# teensy_protocol_xl8r_3_2.net
KiCad netlist of a schematic drawn in EAGLE
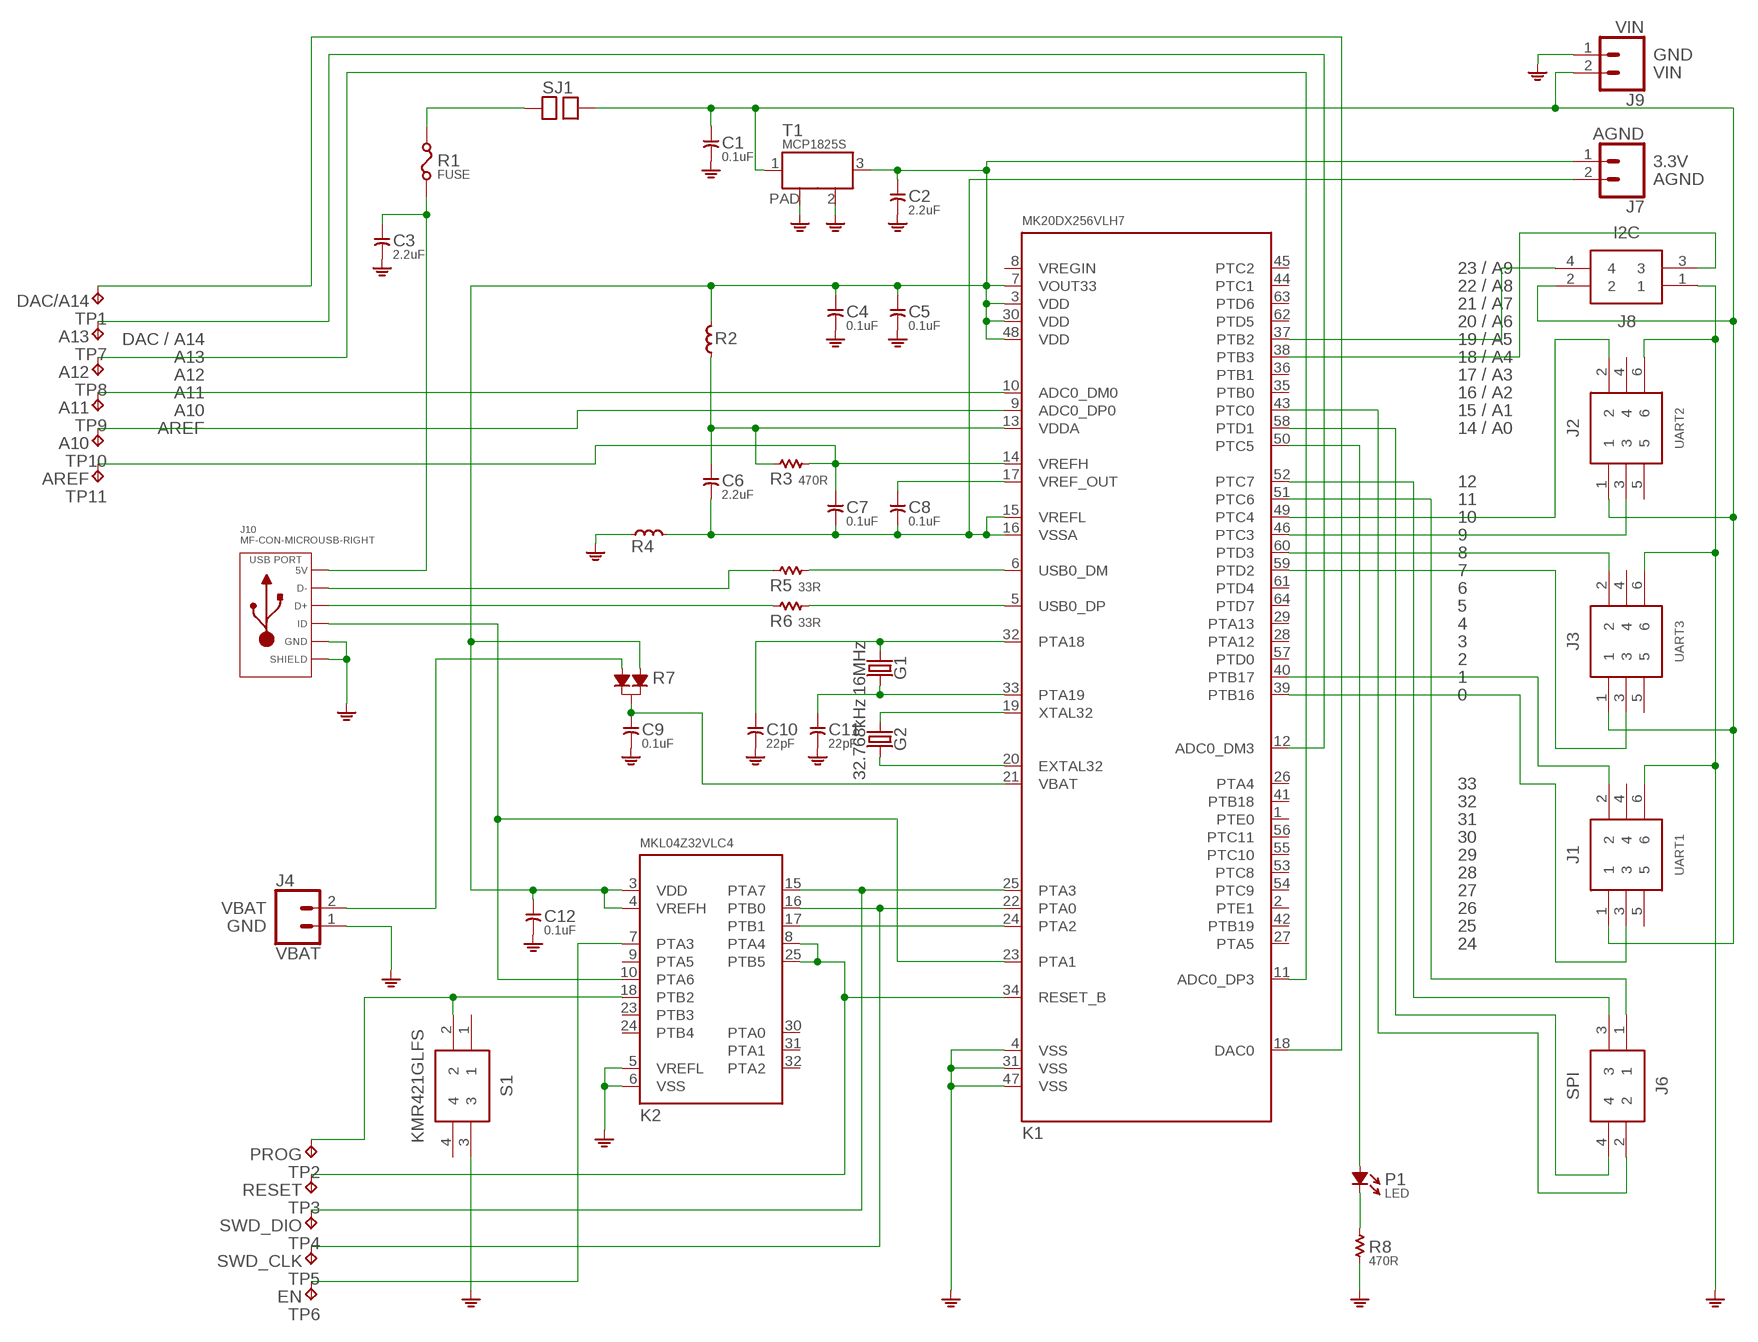
[diagram p0: schematic, sheet 1]

(export (version "E")
  (design (tool "Eeschema 10.0.6"))
  (components
    (comp (ref "C1")
      (value "0.1uF")
      (footprint "eagle-import:C0603")
      (fields (field (name "MF") "Murata Electronics") (field (name "MPN") "GRM188R71C104KA01D"))
      (libsource (lib "eagle-import") (part "CAPACITOR-0.1UF"))
    )
    (comp (ref "C2")
      (value "2.2uF")
      (footprint "eagle-import:C0805")
      (fields (field (name "MF") "Taiyo Yuden") (field (name "MPN") "TMK212B7225KG-TR"))
      (libsource (lib "eagle-import") (part "CAPACITOR-2.2UF"))
    )
    (comp (ref "C3")
      (value "2.2uF")
      (footprint "eagle-import:C0805")
      (fields (field (name "MF") "Taiyo Yuden") (field (name "MPN") "TMK212B7225KG-TR"))
      (libsource (lib "eagle-import") (part "CAPACITOR-2.2UF"))
    )
    (comp (ref "C4")
      (value "0.1uF")
      (footprint "eagle-import:C0603")
      (fields (field (name "MF") "Murata Electronics") (field (name "MPN") "GRM188R71C104KA01D"))
      (libsource (lib "eagle-import") (part "CAPACITOR-0.1UF"))
    )
    (comp (ref "C5")
      (value "0.1uF")
      (footprint "eagle-import:C0603")
      (fields (field (name "MF") "Murata Electronics") (field (name "MPN") "GRM188R71C104KA01D"))
      (libsource (lib "eagle-import") (part "CAPACITOR-0.1UF"))
    )
    (comp (ref "C6")
      (value "2.2uF")
      (footprint "eagle-import:C0805")
      (fields (field (name "MF") "Taiyo Yuden") (field (name "MPN") "TMK212B7225KG-TR"))
      (libsource (lib "eagle-import") (part "CAPACITOR-2.2UF"))
    )
    (comp (ref "C7")
      (value "0.1uF")
      (footprint "eagle-import:C0603")
      (fields (field (name "MF") "Murata Electronics") (field (name "MPN") "GRM188R71C104KA01D"))
      (libsource (lib "eagle-import") (part "CAPACITOR-0.1UF"))
    )
    (comp (ref "C8")
      (value "0.1uF")
      (footprint "eagle-import:C0603")
      (fields (field (name "MF") "Murata Electronics") (field (name "MPN") "GRM188R71C104KA01D"))
      (libsource (lib "eagle-import") (part "CAPACITOR-0.1UF"))
    )
    (comp (ref "C9")
      (value "0.1uF")
      (footprint "eagle-import:C0603")
      (fields (field (name "MF") "Murata Electronics") (field (name "MPN") "GRM188R71C104KA01D"))
      (libsource (lib "eagle-import") (part "CAPACITOR-0.1UF"))
    )
    (comp (ref "C10")
      (value "22pF")
      (footprint "eagle-import:C0603")
      (fields (field (name "MF") "Vishay / Vitramon") (field (name "MPN") "VJ0603A220JXACW1BC"))
      (libsource (lib "eagle-import") (part "CAPACITOR-22PF"))
    )
    (comp (ref "C11")
      (value "22pF")
      (footprint "eagle-import:C0603")
      (fields (field (name "MF") "Vishay / Vitramon") (field (name "MPN") "VJ0603A220JXACW1BC"))
      (libsource (lib "eagle-import") (part "CAPACITOR-22PF"))
    )
    (comp (ref "C12")
      (value "0.1uF")
      (footprint "eagle-import:C0603")
      (fields (field (name "MF") "Murata Electronics") (field (name "MPN") "GRM188R71C104KA01D"))
      (libsource (lib "eagle-import") (part "CAPACITOR-0.1UF"))
    )
    (comp (ref "G1")
      (value "16MHz")
      (footprint "eagle-import:CRYSTAL-SMD-5X3.2-4PAD")
      (libsource (lib "eagle-import") (part "CRYSTAL-16MHZSMD-5X3.2"))
    )
    (comp (ref "G2")
      (value "32.768kHz")
      (footprint "eagle-import:CRYSTAL-SMD-3.2X1.5MM")
      (libsource (lib "eagle-import") (part "CRYSTAL-32.768KHZSMD-3.2X1.5"))
    )
    (comp (ref "J1")
      (value "UART1")
      (footprint "eagle-import:BM06B-GHS-TBT")
      (fields
        (field (name "MANUFACTURER_PART_NUMBER") "BM06B-GHS-TBT(LF)(SN)")
        (field (name "RS_PART_NUMBER") "7521771")
      )
      (libsource (lib "eagle-import") (part "BM06B-GHS-TBT(LF)(SN)"))
    )
    (comp (ref "J2")
      (value "UART2")
      (footprint "eagle-import:BM06B-GHS-TBT")
      (fields
        (field (name "MANUFACTURER_PART_NUMBER") "BM06B-GHS-TBT(LF)(SN)")
        (field (name "RS_PART_NUMBER") "7521771")
      )
      (libsource (lib "eagle-import") (part "BM06B-GHS-TBT(LF)(SN)"))
    )
    (comp (ref "J3")
      (value "UART3")
      (footprint "eagle-import:BM06B-GHS-TBT")
      (fields
        (field (name "MANUFACTURER_PART_NUMBER") "BM06B-GHS-TBT(LF)(SN)")
        (field (name "RS_PART_NUMBER") "7521771")
      )
      (libsource (lib "eagle-import") (part "BM06B-GHS-TBT(LF)(SN)"))
    )
    (comp (ref "J4")
      (value "VBAT")
      (footprint "eagle-import:1X02")
      (libsource (lib "eagle-import") (part "CONN_02"))
    )
    (comp (ref "J6")
      (value "SPI")
      (footprint "eagle-import:BM04B-GHS-TBT")
      (fields
        (field (name "MANUFACTURER_PART_NUMBER") "BM04B-GHS-TBT(LF)(SN)")
        (field (name "RS_PART_NUMBER") "7521769P")
      )
      (libsource (lib "eagle-import") (part "BM04B-GHS-TBT(LF)(SN)"))
    )
    (comp (ref "J7")
      (value "AGND")
      (footprint "eagle-import:1X02")
      (libsource (lib "eagle-import") (part "CONN_02"))
    )
    (comp (ref "J8")
      (value "I2C")
      (footprint "eagle-import:BM04B-GHS-TBT")
      (fields
        (field (name "MANUFACTURER_PART_NUMBER") "BM04B-GHS-TBT(LF)(SN)")
        (field (name "RS_PART_NUMBER") "7521769P")
      )
      (libsource (lib "eagle-import") (part "BM04B-GHS-TBT(LF)(SN)"))
    )
    (comp (ref "J9")
      (value "VIN")
      (footprint "eagle-import:1X02")
      (libsource (lib "eagle-import") (part "CONN_02"))
    )
    (comp (ref "J10")
      (value "MF-CON-MICROUSB-RIGHT")
      (footprint "eagle-import:MICROUSB-RIGHT")
      (fields (field (name "HOUSEPART") "YES"))
      (libsource (lib "eagle-import") (part "USB_MICRO_RIGHT"))
    )
    (comp (ref "K1")
      (value "MK20DX256VLH7")
      (footprint "eagle-import:LQFP64-05")
      (fields (field (name "MF") "NXP"))
      (libsource (lib "eagle-import") (part "MK20DX256VLH7"))
    )
    (comp (ref "K2")
      (value "MKL04Z32VLC4")
      (footprint "eagle-import:LQFP32-08")
      (fields (field (name "MF") "PJRC") (field (name "MPN") "IC_MKL04Z32_TQFP32"))
      (libsource (lib "eagle-import") (part "MKL04Z32VLC4"))
    )
    (comp (ref "P1")
      (value "LED")
      (footprint "eagle-import:LED-0805")
      (fields (field (name "MF") "ROHM Semiconductor") (field (name "MPN") "SML-211DTT86"))
      (libsource (lib "eagle-import") (part "LED"))
    )
    (comp (ref "R1")
      (value "FUSE")
      (footprint "eagle-import:F0805")
      (fields (field (name "MF") "Bel Fuse") (field (name "MPN") "0ZCK0050FF2E"))
      (libsource (lib "eagle-import") (part "FUSE"))
    )
    (comp (ref "R2")
      (value "FERRITE")
      (footprint "eagle-import:L0603")
      (fields (field (name "MF") "Murata Electronics") (field (name "MPN") " BLM18AG601SN1D"))
      (libsource (lib "eagle-import") (part "FERRITE"))
    )
    (comp (ref "R3")
      (value "470R")
      (footprint "eagle-import:R0603")
      (fields (field (name "MF") "Vishay") (field (name "MPN") "CRCW0603470RFKEA"))
      (libsource (lib "eagle-import") (part "RESISTOR-470R"))
    )
    (comp (ref "R4")
      (value "FERRITE")
      (footprint "eagle-import:L0603")
      (fields (field (name "MF") "Murata Electronics") (field (name "MPN") " BLM18AG601SN1D"))
      (libsource (lib "eagle-import") (part "FERRITE"))
    )
    (comp (ref "R5")
      (value "33R")
      (footprint "eagle-import:R0603")
      (fields (field (name "MF") "Panasonic") (field (name "MPN") "ERJ-PA3F33R0V"))
      (libsource (lib "eagle-import") (part "RESISTOR-33R"))
    )
    (comp (ref "R6")
      (value "33R")
      (footprint "eagle-import:R0603")
      (fields (field (name "MF") "Panasonic") (field (name "MPN") "ERJ-PA3F33R0V"))
      (libsource (lib "eagle-import") (part "RESISTOR-33R"))
    )
    (comp (ref "R7")
      (value "DIODE_DUAL")
      (footprint "eagle-import:SOT-23")
      (fields (field (name "MF") "NXP Semiconductors") (field (name "MPN") "BAT54C,215"))
      (libsource (lib "eagle-import") (part "DIODE_DUAL"))
    )
    (comp (ref "R8")
      (value "470R")
      (footprint "eagle-import:R0603")
      (fields (field (name "MF") "Vishay") (field (name "MPN") "CRCW0603470RFKEA"))
      (libsource (lib "eagle-import") (part "RESISTOR-470R"))
    )
    (comp (ref "S1")
      (value "KMR421GLFS")
      (footprint "eagle-import:KMR_2")
      (libsource (lib "eagle-import") (part "KMR421GLFS"))
    )
    (comp (ref "SJ1")
      (value "VUSB")
      (footprint "eagle-import:SOLDERJUMPER")
      (libsource (lib "eagle-import") (part "SOLDERJUMPER"))
    )
    (comp (ref "T1")
      (value "MCP1825S")
      (footprint "eagle-import:SOT-223")
      (fields (field (name "MF") "Microchip Technology") (field (name "MPN") "MCP1825S-3302E/DB"))
      (libsource (lib "eagle-import") (part "LDO"))
    )
    (comp (ref "TP1")
      (value "TPTP06R")
      (footprint "eagle-import:TP06R")
      (fields (field (name "TP_SIGNAL_NAME") "DAC/A14"))
      (libsource (lib "eagle-import") (part "TPTP06R"))
    )
    (comp (ref "TP2")
      (value "TPTP06R")
      (footprint "eagle-import:TP06R")
      (fields (field (name "TP_SIGNAL_NAME") "PROG"))
      (libsource (lib "eagle-import") (part "TPTP06R"))
    )
    (comp (ref "TP3")
      (value "TPTP06R")
      (footprint "eagle-import:TP06R")
      (fields (field (name "TP_SIGNAL_NAME") "RESET"))
      (libsource (lib "eagle-import") (part "TPTP06R"))
    )
    (comp (ref "TP4")
      (value "TPTP06R")
      (footprint "eagle-import:TP06R")
      (fields (field (name "TP_SIGNAL_NAME") "SWD_DIO"))
      (libsource (lib "eagle-import") (part "TPTP06R"))
    )
    (comp (ref "TP5")
      (value "TPTP06R")
      (footprint "eagle-import:TP06R")
      (fields (field (name "TP_SIGNAL_NAME") "SWD_CLK"))
      (libsource (lib "eagle-import") (part "TPTP06R"))
    )
    (comp (ref "TP6")
      (value "TPTP06R")
      (footprint "eagle-import:TP06R")
      (fields (field (name "TP_SIGNAL_NAME") "EN"))
      (libsource (lib "eagle-import") (part "TPTP06R"))
    )
    (comp (ref "TP7")
      (value "TPTP06R")
      (footprint "eagle-import:TP06R")
      (fields (field (name "TP_SIGNAL_NAME") "A13"))
      (libsource (lib "eagle-import") (part "TPTP06R"))
    )
    (comp (ref "TP8")
      (value "TPTP06R")
      (footprint "eagle-import:TP06R")
      (fields (field (name "TP_SIGNAL_NAME") "A12"))
      (libsource (lib "eagle-import") (part "TPTP06R"))
    )
    (comp (ref "TP9")
      (value "TPTP06R")
      (footprint "eagle-import:TP06R")
      (fields (field (name "TP_SIGNAL_NAME") "A11"))
      (libsource (lib "eagle-import") (part "TPTP06R"))
    )
    (comp (ref "TP10")
      (value "TPTP06R")
      (footprint "eagle-import:TP06R")
      (fields (field (name "TP_SIGNAL_NAME") "A10"))
      (libsource (lib "eagle-import") (part "TPTP06R"))
    )
    (comp (ref "TP11")
      (value "TPTP06R")
      (footprint "eagle-import:TP06R")
      (fields (field (name "TP_SIGNAL_NAME") "AREF"))
      (libsource (lib "eagle-import") (part "TPTP06R"))
    )
  )
  (nets
    (net (code "1") (name "GND") (class "Default")
      (node (ref "C1") (pin "2") (pinfunction "2_2") (pintype "passive"))
      (node (ref "C10") (pin "2") (pinfunction "2_2") (pintype "passive"))
      (node (ref "C11") (pin "2") (pinfunction "2_2") (pintype "passive"))
      (node (ref "C12") (pin "2") (pinfunction "2_2") (pintype "passive"))
      (node (ref "C2") (pin "2") (pinfunction "2_2") (pintype "passive"))
      (node (ref "C3") (pin "2") (pinfunction "2_2") (pintype "passive"))
      (node (ref "C4") (pin "2") (pinfunction "2_2") (pintype "passive"))
      (node (ref "C5") (pin "2") (pinfunction "2_2") (pintype "passive"))
      (node (ref "C9") (pin "2") (pinfunction "2_2") (pintype "passive"))
      (node (ref "J1") (pin "6") (pinfunction "6_6") (pintype "passive"))
      (node (ref "J10") (pin "5") (pinfunction "GND_5") (pintype "power_in"))
      (node (ref "J10") (pin "S1") (pinfunction "SLD_S1") (pintype "power_in"))
      (node (ref "J10") (pin "S2") (pinfunction "SLD_S2") (pintype "power_in"))
      (node (ref "J10") (pin "S3") (pinfunction "SLD_S3") (pintype "power_in"))
      (node (ref "J10") (pin "S4") (pinfunction "SLD_S4") (pintype "power_in"))
      (node (ref "J10") (pin "S5") (pinfunction "SLD_S5") (pintype "power_in"))
      (node (ref "J10") (pin "S6") (pinfunction "SLD_S6") (pintype "power_in"))
      (node (ref "J2") (pin "6") (pinfunction "6_6") (pintype "passive"))
      (node (ref "J3") (pin "6") (pinfunction "6_6") (pintype "passive"))
      (node (ref "J4") (pin "1") (pinfunction "1_1") (pintype "passive"))
      (node (ref "J8") (pin "1") (pinfunction "1_1") (pintype "passive"))
      (node (ref "J9") (pin "1") (pinfunction "1_1") (pintype "passive"))
      (node (ref "K1") (pin "31") (pinfunction "VSS_31") (pintype "bidirectional"))
      (node (ref "K1") (pin "4") (pinfunction "VSS_4") (pintype "bidirectional"))
      (node (ref "K1") (pin "47") (pinfunction "VSS_47") (pintype "bidirectional"))
      (node (ref "K2") (pin "5") (pinfunction "VREFL_5") (pintype "bidirectional"))
      (node (ref "K2") (pin "6") (pinfunction "VSS_6") (pintype "bidirectional"))
      (node (ref "R4") (pin "1") (pinfunction "1_1") (pintype "passive"))
      (node (ref "R8") (pin "1") (pinfunction "1_1") (pintype "passive"))
      (node (ref "S1") (pin "3") (pinfunction "3_3") (pintype "passive"))
      (node (ref "T1") (pin "2") (pinfunction "GND_2") (pintype "bidirectional"))
      (node (ref "T1") (pin "PAD") (pinfunction "PAD_PAD") (pintype "bidirectional"))
    )
    (net (code "2") (name "Net-(G1-2)") (class "Default")
      (node (ref "C11") (pin "1") (pinfunction "1_1") (pintype "passive"))
      (node (ref "G1") (pin "3") (pinfunction "2_3") (pintype "passive"))
      (node (ref "K1") (pin "33") (pinfunction "PTA19_33") (pintype "bidirectional"))
    )
    (net (code "3") (name "Net-(G2-1)") (class "Default")
      (node (ref "G2") (pin "P$1") (pinfunction "1_P$1") (pintype "passive"))
      (node (ref "K1") (pin "19") (pinfunction "XTAL32_19") (pintype "bidirectional"))
    )
    (net (code "4") (name "Net-(G2-2)") (class "Default")
      (node (ref "G2") (pin "P$2") (pinfunction "2_P$2") (pintype "passive"))
      (node (ref "K1") (pin "20") (pinfunction "EXTAL32_20") (pintype "bidirectional"))
    )
    (net (code "5") (name "Net-(J4-Pad2)") (class "Default")
      (node (ref "J4") (pin "2") (pinfunction "2_2") (pintype "passive"))
      (node (ref "R7") (pin "2") (pinfunction "2_2") (pintype "bidirectional"))
    )
    (net (code "6") (name "Net-(J10-5V)") (class "Default")
      (node (ref "C3") (pin "1") (pinfunction "1_1") (pintype "passive"))
      (node (ref "J10") (pin "1") (pinfunction "5V_1") (pintype "power_in"))
      (node (ref "R1") (pin "1") (pinfunction "1_1") (pintype "bidirectional"))
    )
    (net (code "7") (name "Net-(J10-D+)") (class "Default")
      (node (ref "J10") (pin "3") (pinfunction "D+_3") (pintype "bidirectional"))
      (node (ref "R6") (pin "1") (pinfunction "1_1") (pintype "passive"))
    )
    (net (code "8") (name "Net-(J10-D-)") (class "Default")
      (node (ref "J10") (pin "2") (pinfunction "D-_2") (pintype "bidirectional"))
      (node (ref "R5") (pin "1") (pinfunction "1_1") (pintype "passive"))
    )
    (net (code "9") (name "Net-(J10-ID)") (class "Default")
      (node (ref "J10") (pin "4") (pinfunction "ID_4") (pintype "bidirectional"))
      (node (ref "K1") (pin "23") (pinfunction "PTA1_23") (pintype "bidirectional"))
      (node (ref "K2") (pin "10") (pinfunction "PTA6_10") (pintype "bidirectional"))
    )
    (net (code "10") (name "Net-(K1-ADC0_DM0)") (class "Default")
      (node (ref "K1") (pin "10") (pinfunction "ADC0_DM0_10") (pintype "bidirectional"))
      (node (ref "TP9") (pin "TP") (pinfunction "TP_TP") (pintype "input"))
    )
    (net (code "11") (name "Net-(K1-ADC0_DM3)") (class "Default")
      (node (ref "K1") (pin "12") (pinfunction "ADC0_DM3_12") (pintype "bidirectional"))
      (node (ref "TP7") (pin "TP") (pinfunction "TP_TP") (pintype "input"))
    )
    (net (code "12") (name "Net-(K1-ADC0_DP0)") (class "Default")
      (node (ref "K1") (pin "9") (pinfunction "ADC0_DP0_9") (pintype "bidirectional"))
      (node (ref "TP10") (pin "TP") (pinfunction "TP_TP") (pintype "input"))
    )
    (net (code "13") (name "Net-(K1-ADC0_DP3)") (class "Default")
      (node (ref "K1") (pin "11") (pinfunction "ADC0_DP3_11") (pintype "bidirectional"))
      (node (ref "TP8") (pin "TP") (pinfunction "TP_TP") (pintype "input"))
    )
    (net (code "14") (name "Net-(K1-DAC0)") (class "Default")
      (node (ref "K1") (pin "18") (pinfunction "DAC0_18") (pintype "bidirectional"))
      (node (ref "TP1") (pin "TP") (pinfunction "TP_TP") (pintype "input"))
    )
    (net (code "15") (name "Net-(K1-PTA0)") (class "Default")
      (node (ref "K1") (pin "22") (pinfunction "PTA0_22") (pintype "bidirectional"))
      (node (ref "K2") (pin "16") (pinfunction "PTB0_16") (pintype "bidirectional"))
      (node (ref "TP5") (pin "TP") (pinfunction "TP_TP") (pintype "input"))
    )
    (net (code "16") (name "Net-(K1-PTA2)") (class "Default")
      (node (ref "K1") (pin "24") (pinfunction "PTA2_24") (pintype "bidirectional"))
      (node (ref "K2") (pin "17") (pinfunction "PTB1_17") (pintype "bidirectional"))
    )
    (net (code "17") (name "Net-(K1-PTA3)") (class "Default")
      (node (ref "K1") (pin "25") (pinfunction "PTA3_25") (pintype "bidirectional"))
      (node (ref "K2") (pin "15") (pinfunction "PTA7_15") (pintype "bidirectional"))
      (node (ref "TP4") (pin "TP") (pinfunction "TP_TP") (pintype "input"))
    )
    (net (code "18") (name "Net-(K1-PTA18)") (class "Default")
      (node (ref "C10") (pin "1") (pinfunction "1_1") (pintype "passive"))
      (node (ref "G1") (pin "1") (pinfunction "1_1") (pintype "passive"))
      (node (ref "K1") (pin "32") (pinfunction "PTA18_32") (pintype "bidirectional"))
    )
    (net (code "19") (name "Net-(K1-PTB2)") (class "Default")
      (node (ref "J8") (pin "4") (pinfunction "4_4") (pintype "passive"))
      (node (ref "K1") (pin "37") (pinfunction "PTB2_37") (pintype "bidirectional"))
    )
    (net (code "20") (name "Net-(K1-PTB3)") (class "Default")
      (node (ref "J8") (pin "3") (pinfunction "3_3") (pintype "passive"))
      (node (ref "K1") (pin "38") (pinfunction "PTB3_38") (pintype "bidirectional"))
    )
    (net (code "21") (name "Net-(K1-PTB16)") (class "Default")
      (node (ref "J1") (pin "3") (pinfunction "3_3") (pintype "passive"))
      (node (ref "K1") (pin "39") (pinfunction "PTB16_39") (pintype "bidirectional"))
    )
    (net (code "22") (name "Net-(K1-PTB17)") (class "Default")
      (node (ref "J1") (pin "2") (pinfunction "2_2") (pintype "passive"))
      (node (ref "K1") (pin "40") (pinfunction "PTB17_40") (pintype "bidirectional"))
    )
    (net (code "23") (name "Net-(K1-PTC0)") (class "Default")
      (node (ref "J6") (pin "2") (pinfunction "2_2") (pintype "passive"))
      (node (ref "K1") (pin "43") (pinfunction "PTC0_43") (pintype "bidirectional"))
    )
    (net (code "24") (name "Net-(K1-PTC3)") (class "Default")
      (node (ref "J2") (pin "3") (pinfunction "3_3") (pintype "passive"))
      (node (ref "K1") (pin "46") (pinfunction "PTC3_46") (pintype "bidirectional"))
    )
    (net (code "25") (name "Net-(K1-PTC4)") (class "Default")
      (node (ref "J2") (pin "2") (pinfunction "2_2") (pintype "passive"))
      (node (ref "K1") (pin "49") (pinfunction "PTC4_49") (pintype "bidirectional"))
    )
    (net (code "26") (name "Net-(K1-PTC5)") (class "Default")
      (node (ref "K1") (pin "50") (pinfunction "PTC5_50") (pintype "bidirectional"))
      (node (ref "P1") (pin "+") (pinfunction "+_+") (pintype "passive"))
    )
    (net (code "27") (name "Net-(K1-PTC6)") (class "Default")
      (node (ref "J6") (pin "1") (pinfunction "1_1") (pintype "passive"))
      (node (ref "K1") (pin "51") (pinfunction "PTC6_51") (pintype "bidirectional"))
    )
    (net (code "28") (name "Net-(K1-PTC7)") (class "Default")
      (node (ref "J6") (pin "3") (pinfunction "3_3") (pintype "passive"))
      (node (ref "K1") (pin "52") (pinfunction "PTC7_52") (pintype "bidirectional"))
    )
    (net (code "29") (name "Net-(K1-PTD1)") (class "Default")
      (node (ref "J6") (pin "4") (pinfunction "4_4") (pintype "passive"))
      (node (ref "K1") (pin "58") (pinfunction "PTD1_58") (pintype "bidirectional"))
    )
    (net (code "30") (name "Net-(K1-PTD2)") (class "Default")
      (node (ref "J3") (pin "3") (pinfunction "3_3") (pintype "passive"))
      (node (ref "K1") (pin "59") (pinfunction "PTD2_59") (pintype "bidirectional"))
    )
    (net (code "31") (name "Net-(K1-PTD3)") (class "Default")
      (node (ref "J3") (pin "2") (pinfunction "2_2") (pintype "passive"))
      (node (ref "K1") (pin "60") (pinfunction "PTD3_60") (pintype "bidirectional"))
    )
    (net (code "32") (name "Net-(K1-RESET_B)") (class "Default")
      (node (ref "K1") (pin "34") (pinfunction "RESET_B_34") (pintype "bidirectional"))
      (node (ref "K2") (pin "25") (pinfunction "PTB5_25") (pintype "bidirectional"))
      (node (ref "K2") (pin "8") (pinfunction "PTA4_8") (pintype "bidirectional"))
      (node (ref "TP3") (pin "TP") (pinfunction "TP_TP") (pintype "input"))
    )
    (net (code "33") (name "Net-(K1-USB0_DM)") (class "Default")
      (node (ref "K1") (pin "6") (pinfunction "USB0_DM_6") (pintype "bidirectional"))
      (node (ref "R5") (pin "2") (pinfunction "2_2") (pintype "passive"))
    )
    (net (code "34") (name "Net-(K1-USB0_DP)") (class "Default")
      (node (ref "K1") (pin "5") (pinfunction "USB0_DP_5") (pintype "bidirectional"))
      (node (ref "R6") (pin "2") (pinfunction "2_2") (pintype "passive"))
    )
    (net (code "35") (name "Net-(K1-VBAT)") (class "Default")
      (node (ref "C9") (pin "1") (pinfunction "1_1") (pintype "passive"))
      (node (ref "K1") (pin "21") (pinfunction "VBAT_21") (pintype "bidirectional"))
      (node (ref "R7") (pin "3") (pinfunction "3_3") (pintype "bidirectional"))
    )
    (net (code "36") (name "Net-(K1-VDDA)") (class "Default")
      (node (ref "C6") (pin "1") (pinfunction "1_1") (pintype "passive"))
      (node (ref "K1") (pin "13") (pinfunction "VDDA_13") (pintype "bidirectional"))
      (node (ref "R2") (pin "1") (pinfunction "1_1") (pintype "passive"))
      (node (ref "R3") (pin "1") (pinfunction "1_1") (pintype "passive"))
    )
    (net (code "37") (name "Net-(K1-VOUT33)") (class "Default")
      (node (ref "C12") (pin "1") (pinfunction "1_1") (pintype "passive"))
      (node (ref "C2") (pin "1") (pinfunction "1_1") (pintype "passive"))
      (node (ref "C4") (pin "1") (pinfunction "1_1") (pintype "passive"))
      (node (ref "C5") (pin "1") (pinfunction "1_1") (pintype "passive"))
      (node (ref "J7") (pin "1") (pinfunction "1_1") (pintype "passive"))
      (node (ref "K1") (pin "3") (pinfunction "VDD_3") (pintype "bidirectional"))
      (node (ref "K1") (pin "30") (pinfunction "VDD_30") (pintype "bidirectional"))
      (node (ref "K1") (pin "48") (pinfunction "VDD_48") (pintype "bidirectional"))
      (node (ref "K1") (pin "7") (pinfunction "VOUT33_7") (pintype "bidirectional"))
      (node (ref "K2") (pin "3") (pinfunction "VDD_3") (pintype "bidirectional"))
      (node (ref "K2") (pin "4") (pinfunction "VREFH_4") (pintype "bidirectional"))
      (node (ref "R2") (pin "2") (pinfunction "2_2") (pintype "passive"))
      (node (ref "R7") (pin "1") (pinfunction "1_1") (pintype "bidirectional"))
      (node (ref "T1") (pin "3") (pinfunction "OUT_3") (pintype "bidirectional"))
    )
    (net (code "38") (name "Net-(K1-VREFH)") (class "Default")
      (node (ref "C7") (pin "1") (pinfunction "1_1") (pintype "passive"))
      (node (ref "K1") (pin "14") (pinfunction "VREFH_14") (pintype "bidirectional"))
      (node (ref "R3") (pin "2") (pinfunction "2_2") (pintype "passive"))
      (node (ref "TP11") (pin "TP") (pinfunction "TP_TP") (pintype "input"))
    )
    (net (code "39") (name "Net-(K1-VREFL)") (class "Default")
      (node (ref "C6") (pin "2") (pinfunction "2_2") (pintype "passive"))
      (node (ref "C7") (pin "2") (pinfunction "2_2") (pintype "passive"))
      (node (ref "C8") (pin "2") (pinfunction "2_2") (pintype "passive"))
      (node (ref "J7") (pin "2") (pinfunction "2_2") (pintype "passive"))
      (node (ref "K1") (pin "15") (pinfunction "VREFL_15") (pintype "bidirectional"))
      (node (ref "K1") (pin "16") (pinfunction "VSSA_16") (pintype "bidirectional"))
      (node (ref "R4") (pin "2") (pinfunction "2_2") (pintype "passive"))
    )
    (net (code "40") (name "Net-(K1-VREF_OUT)") (class "Default")
      (node (ref "C8") (pin "1") (pinfunction "1_1") (pintype "passive"))
      (node (ref "K1") (pin "17") (pinfunction "VREF_OUT_17") (pintype "bidirectional"))
    )
    (net (code "41") (name "Net-(K2-PTA3)") (class "Default")
      (node (ref "K2") (pin "7") (pinfunction "PTA3_7") (pintype "bidirectional"))
      (node (ref "TP6") (pin "TP") (pinfunction "TP_TP") (pintype "input"))
    )
    (net (code "42") (name "Net-(K2-PTB2)") (class "Default")
      (node (ref "K2") (pin "18") (pinfunction "PTB2_18") (pintype "bidirectional"))
      (node (ref "S1") (pin "2") (pinfunction "2_2") (pintype "passive"))
      (node (ref "TP2") (pin "TP") (pinfunction "TP_TP") (pintype "input"))
    )
    (net (code "43") (name "Net-(P1-Pad-)") (class "Default")
      (node (ref "P1") (pin "-") (pinfunction "-_-") (pintype "passive"))
      (node (ref "R8") (pin "2") (pinfunction "2_2") (pintype "passive"))
    )
    (net (code "44") (name "Net-(R1-Pad2)") (class "Default")
      (node (ref "R1") (pin "2") (pinfunction "2_2") (pintype "bidirectional"))
      (node (ref "SJ1") (pin "1") (pinfunction "1_1") (pintype "passive"))
    )
    (net (code "45") (name "Net-(T1-IN)") (class "Default")
      (node (ref "C1") (pin "1") (pinfunction "1_1") (pintype "passive"))
      (node (ref "J1") (pin "1") (pinfunction "1_1") (pintype "passive"))
      (node (ref "J2") (pin "1") (pinfunction "1_1") (pintype "passive"))
      (node (ref "J3") (pin "1") (pinfunction "1_1") (pintype "passive"))
      (node (ref "J8") (pin "2") (pinfunction "2_2") (pintype "passive"))
      (node (ref "J9") (pin "2") (pinfunction "2_2") (pintype "passive"))
      (node (ref "SJ1") (pin "2") (pinfunction "2_2") (pintype "passive"))
      (node (ref "T1") (pin "1") (pinfunction "IN_1") (pintype "bidirectional"))
    )
    (net (code "46") (name "unconnected-(J1-Pad4)") (class "Default")
      (node (ref "J1") (pin "4") (pinfunction "4_4") (pintype "passive"))
    )
    (net (code "47") (name "unconnected-(J1-Pad5)") (class "Default")
      (node (ref "J1") (pin "5") (pinfunction "5_5") (pintype "passive"))
    )
    (net (code "48") (name "unconnected-(J2-Pad4)") (class "Default")
      (node (ref "J2") (pin "4") (pinfunction "4_4") (pintype "passive"))
    )
    (net (code "49") (name "unconnected-(J2-Pad5)") (class "Default")
      (node (ref "J2") (pin "5") (pinfunction "5_5") (pintype "passive"))
    )
    (net (code "50") (name "unconnected-(J3-Pad4)") (class "Default")
      (node (ref "J3") (pin "4") (pinfunction "4_4") (pintype "passive"))
    )
    (net (code "51") (name "unconnected-(J3-Pad5)") (class "Default")
      (node (ref "J3") (pin "5") (pinfunction "5_5") (pintype "passive"))
    )
    (net (code "52") (name "unconnected-(K1-PTA4-Pad26)") (class "Default")
      (node (ref "K1") (pin "26") (pinfunction "PTA4_26") (pintype "bidirectional"))
    )
    (net (code "53") (name "unconnected-(K1-PTA5-Pad27)") (class "Default")
      (node (ref "K1") (pin "27") (pinfunction "PTA5_27") (pintype "bidirectional"))
    )
    (net (code "54") (name "unconnected-(K1-PTA12-Pad28)") (class "Default")
      (node (ref "K1") (pin "28") (pinfunction "PTA12_28") (pintype "bidirectional"))
    )
    (net (code "55") (name "unconnected-(K1-PTA13-Pad29)") (class "Default")
      (node (ref "K1") (pin "29") (pinfunction "PTA13_29") (pintype "bidirectional"))
    )
    (net (code "56") (name "unconnected-(K1-PTB0-Pad35)") (class "Default")
      (node (ref "K1") (pin "35") (pinfunction "PTB0_35") (pintype "bidirectional"))
    )
    (net (code "57") (name "unconnected-(K1-PTB1-Pad36)") (class "Default")
      (node (ref "K1") (pin "36") (pinfunction "PTB1_36") (pintype "bidirectional"))
    )
    (net (code "58") (name "unconnected-(K1-PTB18-Pad41)") (class "Default")
      (node (ref "K1") (pin "41") (pinfunction "PTB18_41") (pintype "bidirectional"))
    )
    (net (code "59") (name "unconnected-(K1-PTB19-Pad42)") (class "Default")
      (node (ref "K1") (pin "42") (pinfunction "PTB19_42") (pintype "bidirectional"))
    )
    (net (code "60") (name "unconnected-(K1-PTC1-Pad44)") (class "Default")
      (node (ref "K1") (pin "44") (pinfunction "PTC1_44") (pintype "bidirectional"))
    )
    (net (code "61") (name "unconnected-(K1-PTC2-Pad45)") (class "Default")
      (node (ref "K1") (pin "45") (pinfunction "PTC2_45") (pintype "bidirectional"))
    )
    (net (code "62") (name "unconnected-(K1-PTC8-Pad53)") (class "Default")
      (node (ref "K1") (pin "53") (pinfunction "PTC8_53") (pintype "bidirectional"))
    )
    (net (code "63") (name "unconnected-(K1-PTC9-Pad54)") (class "Default")
      (node (ref "K1") (pin "54") (pinfunction "PTC9_54") (pintype "bidirectional"))
    )
    (net (code "64") (name "unconnected-(K1-PTC10-Pad55)") (class "Default")
      (node (ref "K1") (pin "55") (pinfunction "PTC10_55") (pintype "bidirectional"))
    )
    (net (code "65") (name "unconnected-(K1-PTC11-Pad56)") (class "Default")
      (node (ref "K1") (pin "56") (pinfunction "PTC11_56") (pintype "bidirectional"))
    )
    (net (code "66") (name "unconnected-(K1-PTD0-Pad57)") (class "Default")
      (node (ref "K1") (pin "57") (pinfunction "PTD0_57") (pintype "bidirectional"))
    )
    (net (code "67") (name "unconnected-(K1-PTD4-Pad61)") (class "Default")
      (node (ref "K1") (pin "61") (pinfunction "PTD4_61") (pintype "bidirectional"))
    )
    (net (code "68") (name "unconnected-(K1-PTD5-Pad62)") (class "Default")
      (node (ref "K1") (pin "62") (pinfunction "PTD5_62") (pintype "bidirectional"))
    )
    (net (code "69") (name "unconnected-(K1-PTD6-Pad63)") (class "Default")
      (node (ref "K1") (pin "63") (pinfunction "PTD6_63") (pintype "bidirectional"))
    )
    (net (code "70") (name "unconnected-(K1-PTD7-Pad64)") (class "Default")
      (node (ref "K1") (pin "64") (pinfunction "PTD7_64") (pintype "bidirectional"))
    )
    (net (code "71") (name "unconnected-(K1-PTE0-Pad1)") (class "Default")
      (node (ref "K1") (pin "1") (pinfunction "PTE0_1") (pintype "bidirectional"))
    )
    (net (code "72") (name "unconnected-(K1-PTE1-Pad2)") (class "Default")
      (node (ref "K1") (pin "2") (pinfunction "PTE1_2") (pintype "bidirectional"))
    )
    (net (code "73") (name "unconnected-(K1-VREGIN-Pad8)") (class "Default")
      (node (ref "K1") (pin "8") (pinfunction "VREGIN_8") (pintype "bidirectional"))
    )
    (net (code "74") (name "unconnected-(K2-PTA0-Pad30)") (class "Default")
      (node (ref "K2") (pin "30") (pinfunction "PTA0_30") (pintype "bidirectional"))
    )
    (net (code "75") (name "unconnected-(K2-PTA1-Pad31)") (class "Default")
      (node (ref "K2") (pin "31") (pinfunction "PTA1_31") (pintype "bidirectional"))
    )
    (net (code "76") (name "unconnected-(K2-PTA2-Pad32)") (class "Default")
      (node (ref "K2") (pin "32") (pinfunction "PTA2_32") (pintype "bidirectional"))
    )
    (net (code "77") (name "unconnected-(K2-PTA5-Pad9)") (class "Default")
      (node (ref "K2") (pin "9") (pinfunction "PTA5_9") (pintype "bidirectional"))
    )
    (net (code "78") (name "unconnected-(K2-PTB3-Pad23)") (class "Default")
      (node (ref "K2") (pin "23") (pinfunction "PTB3_23") (pintype "bidirectional"))
    )
    (net (code "79") (name "unconnected-(K2-PTB4-Pad24)") (class "Default")
      (node (ref "K2") (pin "24") (pinfunction "PTB4_24") (pintype "bidirectional"))
    )
    (net (code "80") (name "unconnected-(S1-Pad1)") (class "Default")
      (node (ref "S1") (pin "1") (pinfunction "1_1") (pintype "passive"))
    )
    (net (code "81") (name "unconnected-(S1-Pad4)") (class "Default")
      (node (ref "S1") (pin "4") (pinfunction "4_4") (pintype "passive"))
    )
  )
)
